# FinalSubNode.net
KiCad netlist of a schematic drawn in Altium Designer
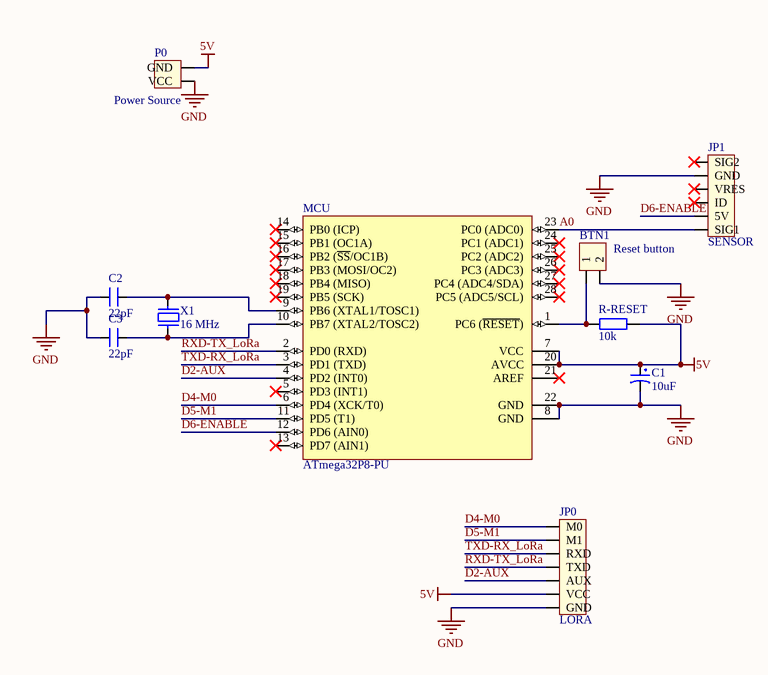
[diagram p0: FinalSubNode.SchDoc]

(export (version "E")
  (design (tool "Eeschema 10.0.6"))
  (components
    (comp (ref "BTN1")
      (value "Reset button")
      (footprint "HED2")
      (description "Header 2 (Green)")
      (libsource (lib "") (part "Hed2_1"))
    )
    (comp (ref "C1")
      (value "10uF")
      (footprint "CP1/2")
      (description "Cap P  0,1uF < 22uF , 16 - 50V")
      (libsource (lib "syhaunguyen") (part "CP1"))
    )
    (comp (ref "C2")
      (value "22pF")
      (footprint "CN1")
      (description "Cap np  1pF - 472pF")
      (libsource (lib "syhaunguyen") (part "CN1"))
    )
    (comp (ref "C3")
      (value "22pF")
      (footprint "CN1")
      (description "Cap np  1pF - 472pF")
      (libsource (lib "syhaunguyen") (part "CN1"))
    )
    (comp (ref "JP0")
      (value "LORA")
      (footprint "CON7")
      (description "Connector 7")
      (libsource (lib "syhaunguyen") (part "Con7"))
    )
    (comp (ref "JP1")
      (value "SENSOR")
      (footprint "CON6")
      (description "Connector 6")
      (libsource (lib "syhaunguyen") (part "Con6"))
    )
    (comp (ref "MCU")
      (value "ATmega32P8-PU")
      (footprint "DIP28/W0.3")
      (description "8-Bit AVR Microcontroller with 8K Bytes of In-System Programmable Flash Memory")
      (libsource (lib "syhaunguyen") (part "ATmega8-L"))
    )
    (comp (ref "P0")
      (value "Power Source")
      (footprint "HED2")
      (description "Header 2 (Green)")
      (libsource (lib "syhaunguyen") (part "Hed2"))
    )
    (comp (ref "R-RESET")
      (value "10k")
      (footprint "R1/4W")
      (description "Resistor 1/4W")
      (libsource (lib "syhaunguyen") (part "R1/4W"))
    )
    (comp (ref "X1")
      (value "16 MHz")
      (footprint "XT2")
      (description "Crystal For all Crystal 2pin.")
      (libsource (lib "syhaunguyen") (part "XT2"))
    )
  )
  (nets
    (net (code "1") (name "/A0") (class "Default")
      (node (ref "JP1") (pin "6") (pinfunction "SIG1_6") (pintype "passive"))
      (node (ref "MCU") (pin "23") (pinfunction "PC0_(ADC0)_23") (pintype "bidirectional"))
    )
    (net (code "2") (name "/D2-AUX") (class "Default")
      (node (ref "JP0") (pin "5") (pinfunction "AUX_5") (pintype "passive"))
      (node (ref "MCU") (pin "4") (pinfunction "PD2_(INT0)_4") (pintype "bidirectional"))
    )
    (net (code "3") (name "/D4-M0") (class "Default")
      (node (ref "JP0") (pin "1") (pinfunction "M0_1") (pintype "passive"))
      (node (ref "MCU") (pin "6") (pinfunction "PD4_(XCK/T0)_6") (pintype "bidirectional"))
    )
    (net (code "4") (name "/D5-M1") (class "Default")
      (node (ref "JP0") (pin "2") (pinfunction "M1_2") (pintype "passive"))
      (node (ref "MCU") (pin "11") (pinfunction "PD5_(T1)_11") (pintype "bidirectional"))
    )
    (net (code "5") (name "/D6-ENABLE") (class "Default")
      (node (ref "JP1") (pin "5") (pinfunction "5V_5") (pintype "passive"))
      (node (ref "MCU") (pin "12") (pinfunction "PD6_(AIN0)_12") (pintype "bidirectional"))
    )
    (net (code "6") (name "/RXD-TX_LoRa") (class "Default")
      (node (ref "JP0") (pin "4") (pinfunction "TXD_4") (pintype "passive"))
      (node (ref "MCU") (pin "2") (pinfunction "PD0_(RXD)_2") (pintype "bidirectional"))
    )
    (net (code "7") (name "/TXD-RX_LoRa") (class "Default")
      (node (ref "JP0") (pin "3") (pinfunction "RXD_3") (pintype "passive"))
      (node (ref "MCU") (pin "3") (pinfunction "PD1_(TXD)_3") (pintype "bidirectional"))
    )
    (net (code "8") (name "5V") (class "Default")
      (node (ref "C1") (pin "1") (pinfunction "1_1") (pintype "passive"))
      (node (ref "JP0") (pin "6") (pinfunction "VCC_6") (pintype "passive"))
      (node (ref "MCU") (pin "20") (pinfunction "AVCC_20") (pintype "power_in"))
      (node (ref "MCU") (pin "7") (pinfunction "VCC_7") (pintype "power_in"))
      (node (ref "P0") (pin "2") (pinfunction "GND_2") (pintype "passive"))
      (node (ref "R-RESET") (pin "2") (pinfunction "2_2") (pintype "passive"))
    )
    (net (code "9") (name "GND") (class "Default")
      (node (ref "BTN1") (pin "2") (pinfunction "2_2") (pintype "passive"))
      (node (ref "C1") (pin "2") (pinfunction "2_2") (pintype "passive"))
      (node (ref "C2") (pin "1") (pinfunction "1_1") (pintype "passive"))
      (node (ref "C3") (pin "1") (pinfunction "1_1") (pintype "passive"))
      (node (ref "JP0") (pin "7") (pinfunction "GND_7") (pintype "passive"))
      (node (ref "JP1") (pin "2") (pinfunction "GND_2") (pintype "passive"))
      (node (ref "MCU") (pin "22") (pinfunction "GND_22") (pintype "power_in"))
      (node (ref "MCU") (pin "8") (pinfunction "GND_8") (pintype "power_in"))
      (node (ref "P0") (pin "1") (pinfunction "VCC_1") (pintype "passive"))
    )
    (net (code "10") (name "Net-(MCU-PB6_(XTAL1{slash}TOSC1))") (class "Default")
      (node (ref "C2") (pin "2") (pinfunction "2_2") (pintype "passive"))
      (node (ref "MCU") (pin "9") (pinfunction "PB6_(XTAL1/TOSC1)_9") (pintype "bidirectional"))
      (node (ref "X1") (pin "2") (pinfunction "2_2") (pintype "passive"))
    )
    (net (code "11") (name "Net-(MCU-PB7_(XTAL2{slash}TOSC2))") (class "Default")
      (node (ref "C3") (pin "2") (pinfunction "2_2") (pintype "passive"))
      (node (ref "MCU") (pin "10") (pinfunction "PB7_(XTAL2/TOSC2)_10") (pintype "bidirectional"))
      (node (ref "X1") (pin "1") (pinfunction "1_1") (pintype "passive"))
    )
    (net (code "12") (name "Net-(MCU-PC6_(~{RESET}))") (class "Default")
      (node (ref "BTN1") (pin "1") (pinfunction "1_1") (pintype "passive"))
      (node (ref "MCU") (pin "1") (pinfunction "PC6_(~{RESET})_1") (pintype "bidirectional"))
      (node (ref "R-RESET") (pin "1") (pinfunction "1_1") (pintype "passive"))
    )
    (net (code "13") (name "unconnected-(JP1-ID-Pad4)") (class "Default")
      (node (ref "JP1") (pin "4") (pinfunction "ID_4") (pintype "passive+no_connect"))
    )
    (net (code "14") (name "unconnected-(JP1-SIG2-Pad1)") (class "Default")
      (node (ref "JP1") (pin "1") (pinfunction "SIG2_1") (pintype "passive+no_connect"))
    )
    (net (code "15") (name "unconnected-(JP1-VRES-Pad3)") (class "Default")
      (node (ref "JP1") (pin "3") (pinfunction "VRES_3") (pintype "passive+no_connect"))
    )
    (net (code "16") (name "unconnected-(MCU-AREF-Pad21)") (class "Default")
      (node (ref "MCU") (pin "21") (pinfunction "AREF_21") (pintype "passive+no_connect"))
    )
    (net (code "17") (name "unconnected-(MCU-PB0_(ICP)-Pad14)") (class "Default")
      (node (ref "MCU") (pin "14") (pinfunction "PB0_(ICP)_14") (pintype "bidirectional+no_connect"))
    )
    (net (code "18") (name "unconnected-(MCU-PB1_(OC1A)-Pad15)") (class "Default")
      (node (ref "MCU") (pin "15") (pinfunction "PB1_(OC1A)_15") (pintype "bidirectional+no_connect"))
    )
    (net (code "19") (name "unconnected-(MCU-PB2_(~{SS}{slash}OC1B)-Pad16)") (class "Default")
      (node (ref "MCU") (pin "16") (pinfunction "PB2_(~{SS}/OC1B)_16") (pintype "bidirectional+no_connect"))
    )
    (net (code "20") (name "unconnected-(MCU-PB3_(MOSI{slash}OC2)-Pad17)") (class "Default")
      (node (ref "MCU") (pin "17") (pinfunction "PB3_(MOSI/OC2)_17") (pintype "bidirectional+no_connect"))
    )
    (net (code "21") (name "unconnected-(MCU-PB4_(MISO)-Pad18)") (class "Default")
      (node (ref "MCU") (pin "18") (pinfunction "PB4_(MISO)_18") (pintype "bidirectional+no_connect"))
    )
    (net (code "22") (name "unconnected-(MCU-PB5_(SCK)-Pad19)") (class "Default")
      (node (ref "MCU") (pin "19") (pinfunction "PB5_(SCK)_19") (pintype "bidirectional+no_connect"))
    )
    (net (code "23") (name "unconnected-(MCU-PC1_(ADC1)-Pad24)") (class "Default")
      (node (ref "MCU") (pin "24") (pinfunction "PC1_(ADC1)_24") (pintype "bidirectional+no_connect"))
    )
    (net (code "24") (name "unconnected-(MCU-PC2_(ADC2)-Pad25)") (class "Default")
      (node (ref "MCU") (pin "25") (pinfunction "PC2_(ADC2)_25") (pintype "bidirectional+no_connect"))
    )
    (net (code "25") (name "unconnected-(MCU-PC3_(ADC3)-Pad26)") (class "Default")
      (node (ref "MCU") (pin "26") (pinfunction "PC3_(ADC3)_26") (pintype "bidirectional+no_connect"))
    )
    (net (code "26") (name "unconnected-(MCU-PC4_(ADC4{slash}SDA)-Pad27)") (class "Default")
      (node (ref "MCU") (pin "27") (pinfunction "PC4_(ADC4/SDA)_27") (pintype "bidirectional+no_connect"))
    )
    (net (code "27") (name "unconnected-(MCU-PC5_(ADC5{slash}SCL)-Pad28)") (class "Default")
      (node (ref "MCU") (pin "28") (pinfunction "PC5_(ADC5/SCL)_28") (pintype "bidirectional+no_connect"))
    )
    (net (code "28") (name "unconnected-(MCU-PD3_(INT1)-Pad5)") (class "Default")
      (node (ref "MCU") (pin "5") (pinfunction "PD3_(INT1)_5") (pintype "bidirectional+no_connect"))
    )
    (net (code "29") (name "unconnected-(MCU-PD7_(AIN1)-Pad13)") (class "Default")
      (node (ref "MCU") (pin "13") (pinfunction "PD7_(AIN1)_13") (pintype "bidirectional+no_connect"))
    )
  )
)
